# AJH_2v_v1_03.net
KiCad netlist of a schematic drawn in EAGLE
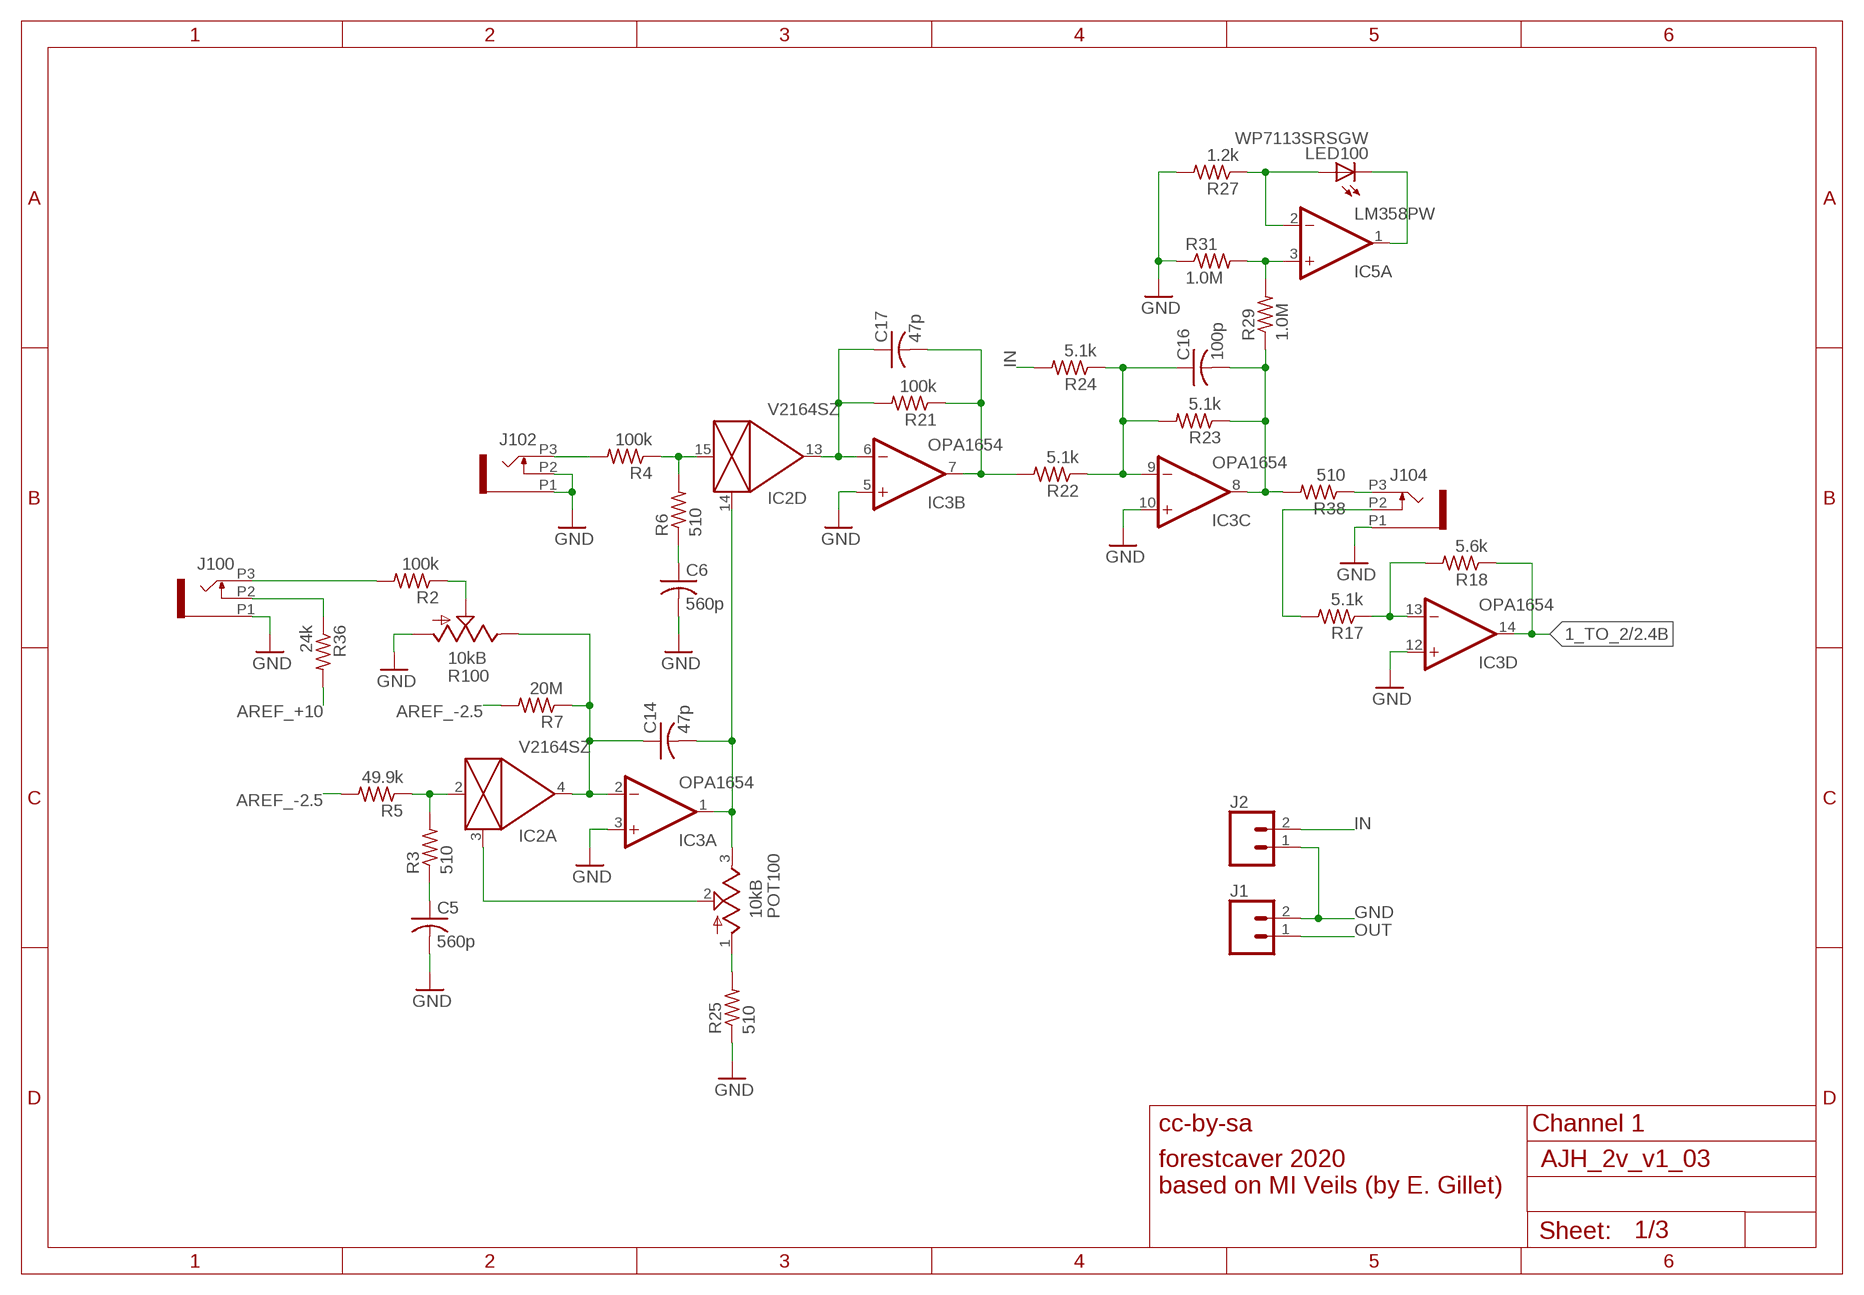
[diagram p0: schematic, sheet 1]
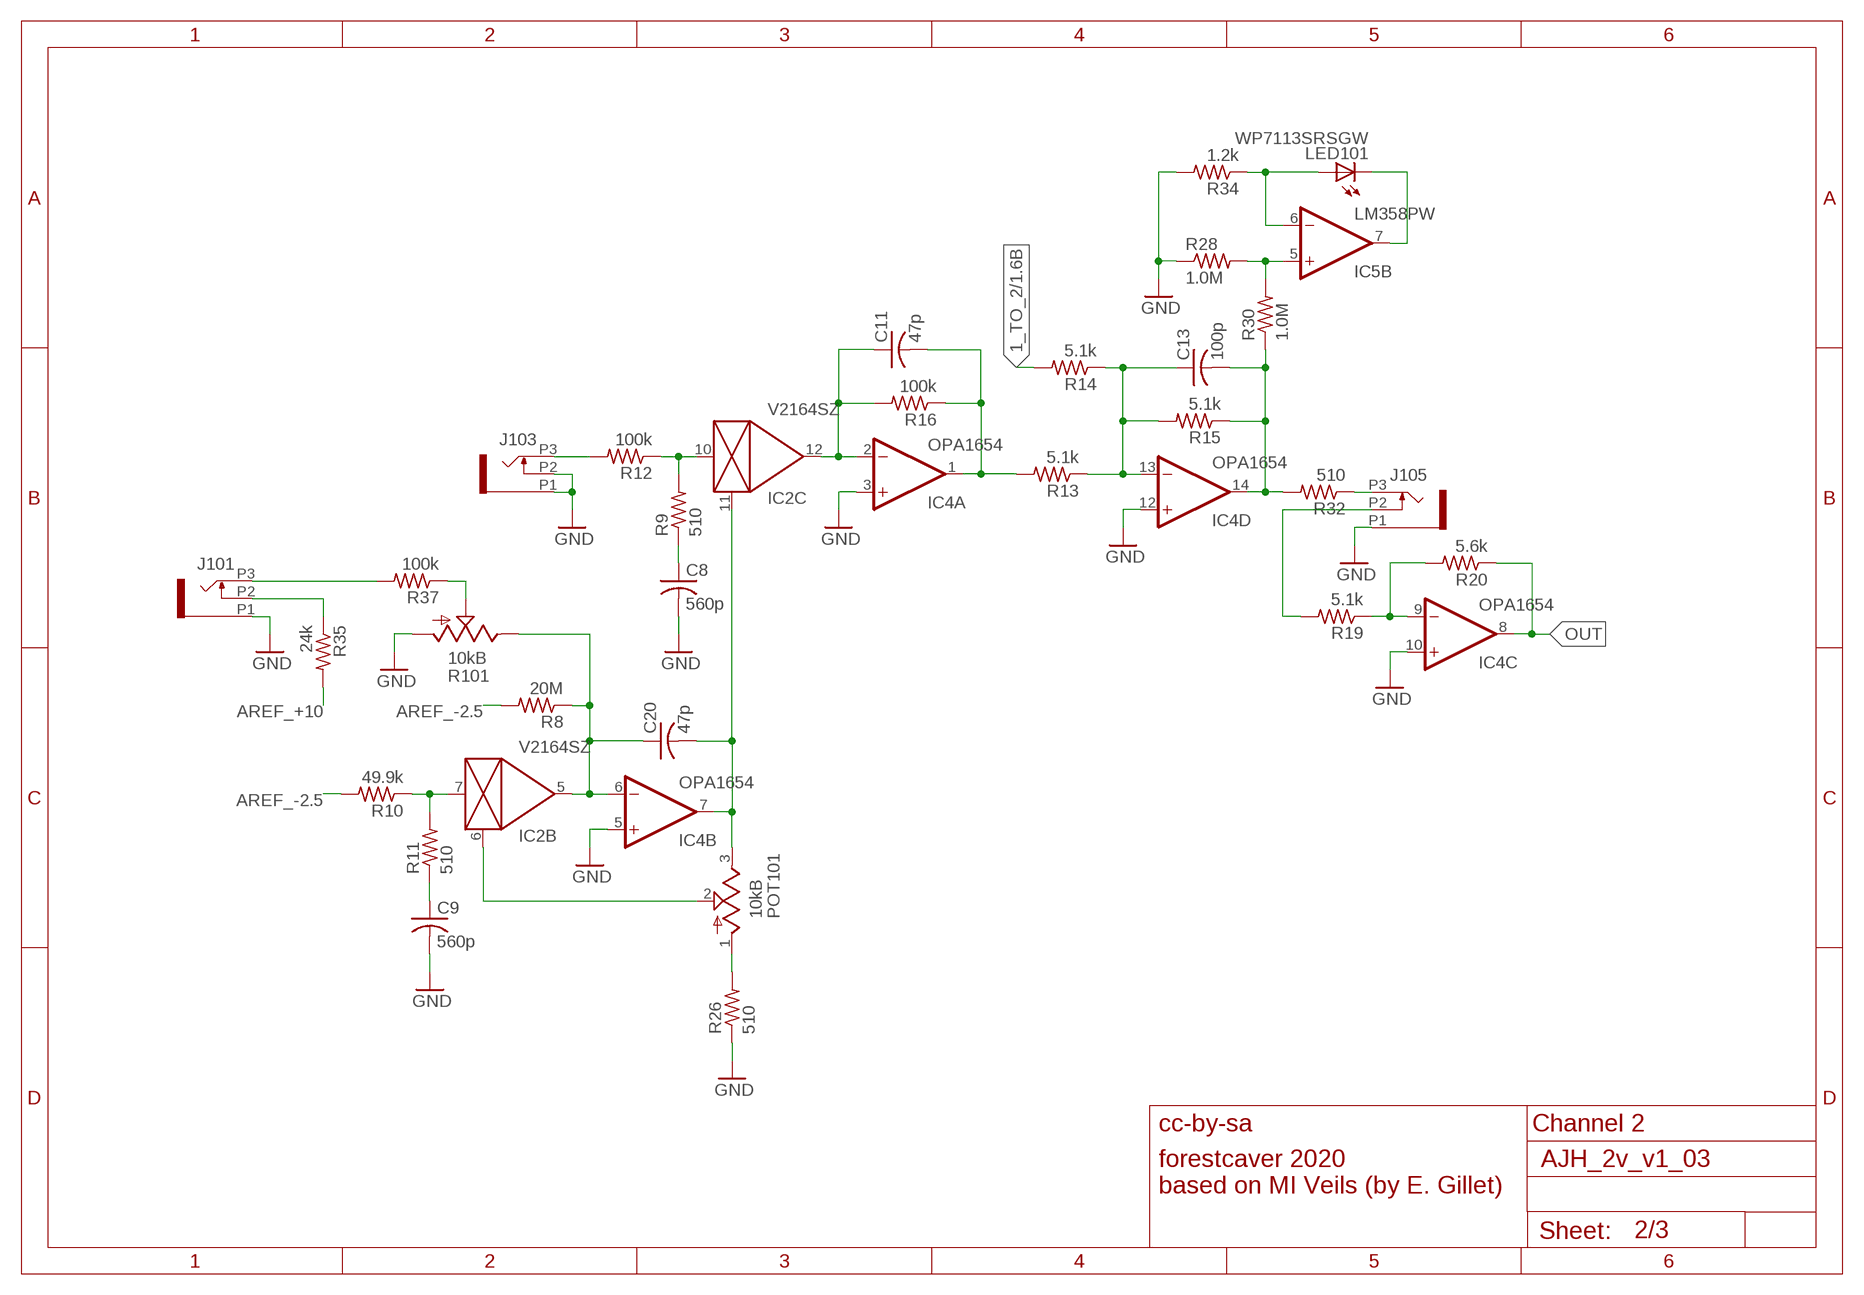
[diagram p1: schematic, sheet 2]
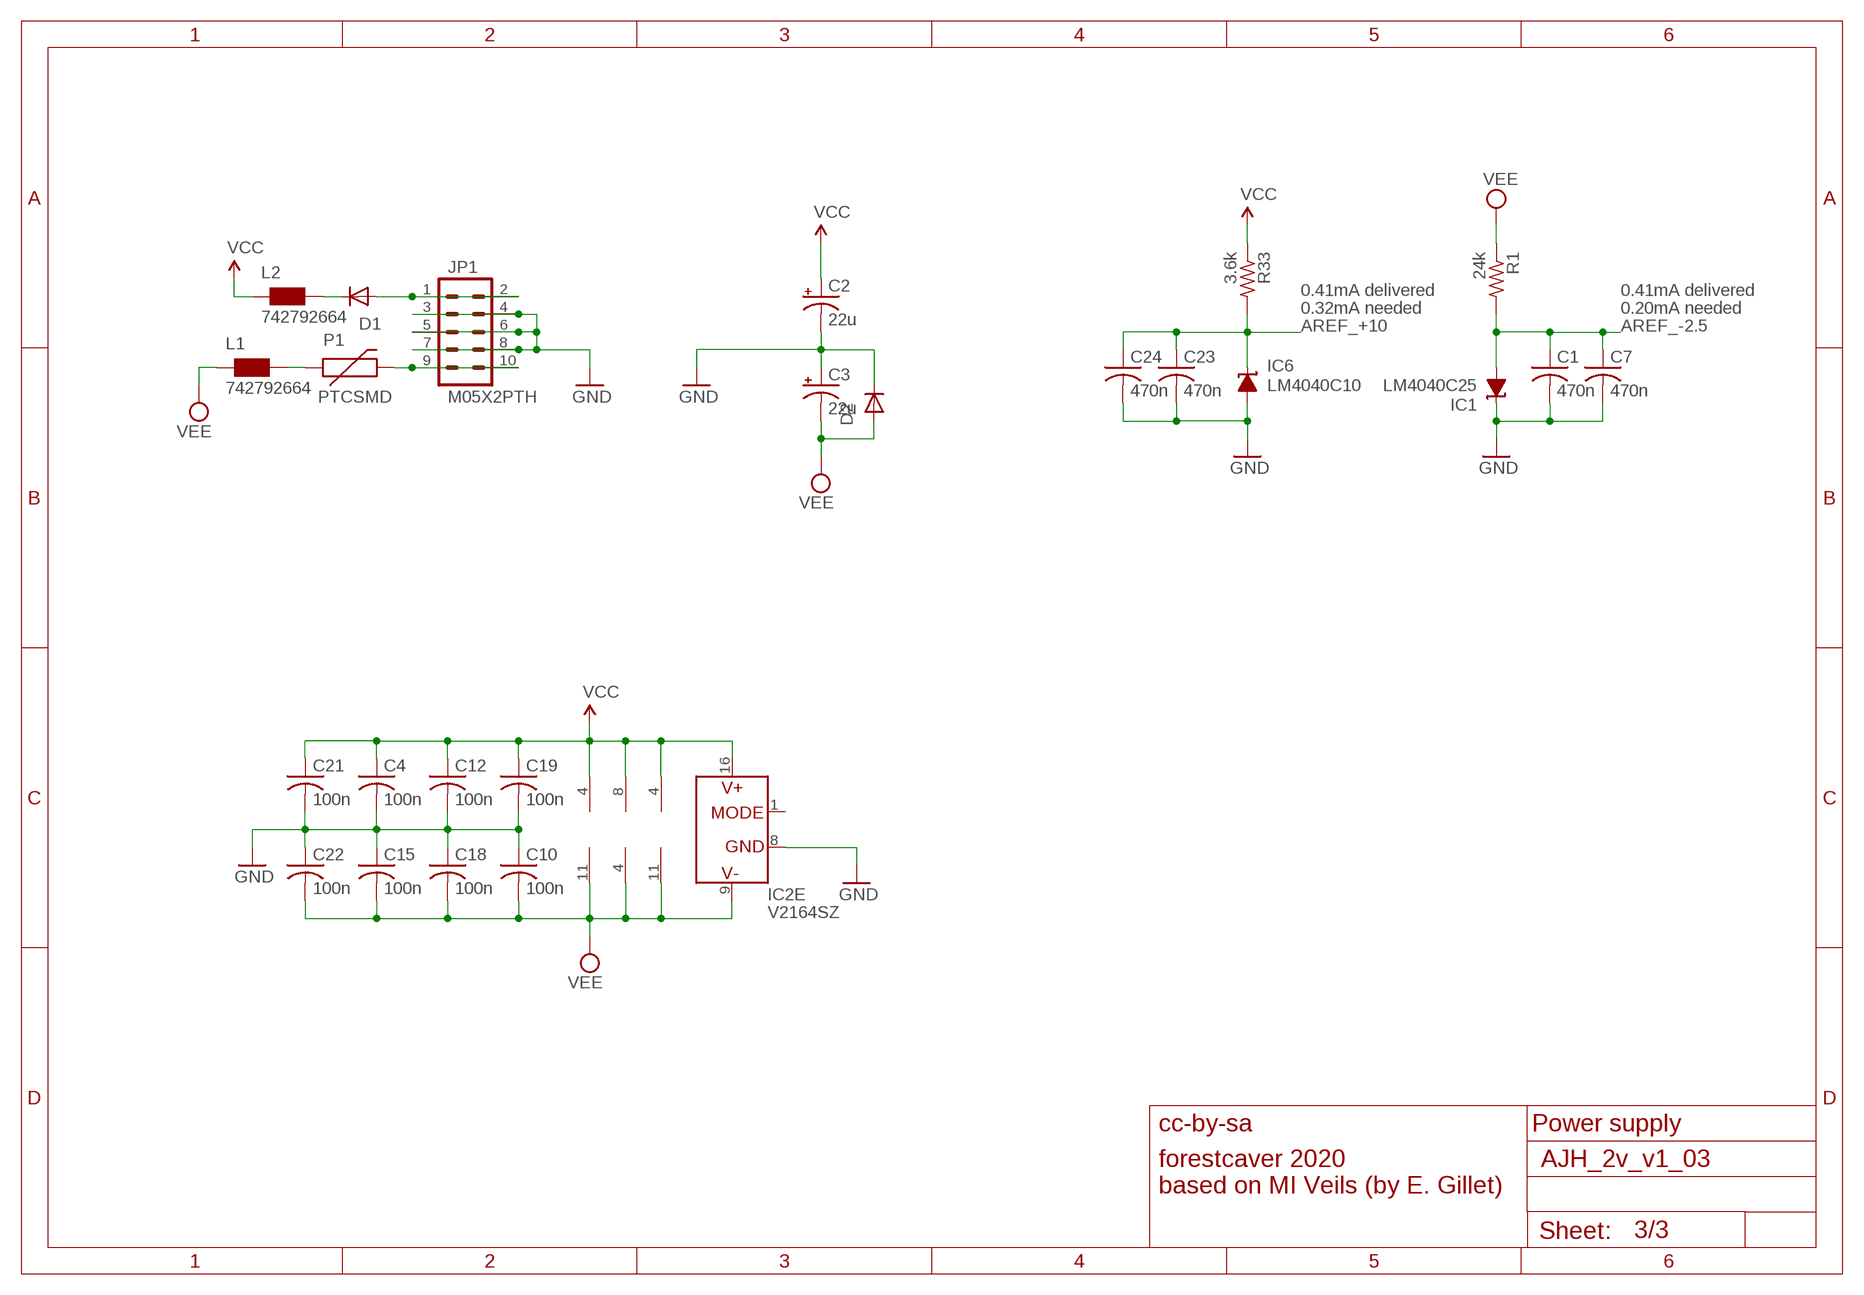
[diagram p2: schematic, sheet 3]

(export (version "E")
  (design (tool "Eeschema 10.0.6"))
  (components
    (comp (ref "C5")
      (value "560p")
      (footprint "eagle-import:C0402")
      (libsource (lib "eagle-import") (part "C-USC0402"))
    )
    (comp (ref "C6")
      (value "560p")
      (footprint "eagle-import:C0402")
      (libsource (lib "eagle-import") (part "C-USC0402"))
    )
    (comp (ref "C14")
      (value "47p")
      (footprint "eagle-import:C0402")
      (libsource (lib "eagle-import") (part "C-USC0402"))
    )
    (comp (ref "C16")
      (value "100p")
      (footprint "eagle-import:C0402")
      (libsource (lib "eagle-import") (part "C-USC0402"))
    )
    (comp (ref "C17")
      (value "47p")
      (footprint "eagle-import:C0402")
      (libsource (lib "eagle-import") (part "C-USC0402"))
    )
    (comp (ref "IC2")
      (value "V2164SZ")
      (footprint "eagle-import:SOIC16N")
      (libsource (lib "eagle-import") (part "SSM2164S"))
    )
    (comp (ref "IC3")
      (value "OPA1654")
      (footprint "eagle-import:TSSOP14")
      (libsource (lib "eagle-import") (part "TL074PW"))
    )
    (comp (ref "IC5")
      (value "LM358PW")
      (footprint "eagle-import:TSSOP8")
      (libsource (lib "eagle-import") (part "TL072PW"))
    )
    (comp (ref "J1")
      (value "CONN_02")
      (footprint "eagle-import:1X02")
      (libsource (lib "eagle-import") (part "CONN_02"))
    )
    (comp (ref "J2")
      (value "CONN_02")
      (footprint "eagle-import:1X02")
      (libsource (lib "eagle-import") (part "CONN_02"))
    )
    (comp (ref "J100")
      (value "PJ301_THONKICONN6")
      (footprint "eagle-import:WQP_PJ_301M6")
      (libsource (lib "eagle-import") (part "PJ301_THONKICONN6"))
    )
    (comp (ref "J102")
      (value "PJ301_THONKICONN6")
      (footprint "eagle-import:WQP_PJ_301M6")
      (libsource (lib "eagle-import") (part "PJ301_THONKICONN6"))
    )
    (comp (ref "J104")
      (value "PJ301_THONKICONN6")
      (footprint "eagle-import:WQP_PJ_301M6")
      (libsource (lib "eagle-import") (part "PJ301_THONKICONN6"))
    )
    (comp (ref "LED100")
      (value "WP7113SRSGW")
      (footprint "eagle-import:LED5MM")
      (libsource (lib "eagle-import") (part "LED5MM"))
    )
    (comp (ref "POT100")
      (value "10kB")
      (footprint "eagle-import:ALPS_POT_NOHOLE")
      (libsource (lib "eagle-import") (part "POT_VERTICALNOHOLE"))
    )
    (comp (ref "R2")
      (value "100k")
      (footprint "eagle-import:R0402")
      (libsource (lib "eagle-import") (part "R-US_R0402"))
    )
    (comp (ref "R3")
      (value "510")
      (footprint "eagle-import:R0402")
      (libsource (lib "eagle-import") (part "R-US_R0402"))
    )
    (comp (ref "R4")
      (value "100k")
      (footprint "eagle-import:R0402")
      (libsource (lib "eagle-import") (part "R-US_R0402"))
    )
    (comp (ref "R5")
      (value "49.9k")
      (footprint "eagle-import:R0402")
      (libsource (lib "eagle-import") (part "R-US_R0402"))
    )
    (comp (ref "R6")
      (value "510")
      (footprint "eagle-import:R0402")
      (libsource (lib "eagle-import") (part "R-US_R0402"))
    )
    (comp (ref "R7")
      (value "20M")
      (footprint "eagle-import:R0402")
      (libsource (lib "eagle-import") (part "R-US_R0402"))
    )
    (comp (ref "R17")
      (value "5.1k")
      (footprint "eagle-import:R0402")
      (libsource (lib "eagle-import") (part "R-US_R0402"))
    )
    (comp (ref "R18")
      (value "5.6k")
      (footprint "eagle-import:R0402")
      (libsource (lib "eagle-import") (part "R-US_R0402"))
    )
    (comp (ref "R21")
      (value "100k")
      (footprint "eagle-import:R0402")
      (libsource (lib "eagle-import") (part "R-US_R0402"))
    )
    (comp (ref "R22")
      (value "5.1k")
      (footprint "eagle-import:R0402")
      (libsource (lib "eagle-import") (part "R-US_R0402"))
    )
    (comp (ref "R23")
      (value "5.1k")
      (footprint "eagle-import:R0402")
      (libsource (lib "eagle-import") (part "R-US_R0402"))
    )
    (comp (ref "R24")
      (value "5.1k")
      (footprint "eagle-import:R0402")
      (libsource (lib "eagle-import") (part "R-US_R0402"))
    )
    (comp (ref "R25")
      (value "510")
      (footprint "eagle-import:R0402")
      (libsource (lib "eagle-import") (part "R-US_R0402"))
    )
    (comp (ref "R27")
      (value "1.2k")
      (footprint "eagle-import:R0402")
      (libsource (lib "eagle-import") (part "R-US_R0402"))
    )
    (comp (ref "R29")
      (value "1.0M")
      (footprint "eagle-import:R0402")
      (libsource (lib "eagle-import") (part "R-US_R0402"))
    )
    (comp (ref "R31")
      (value "1.0M")
      (footprint "eagle-import:R0402")
      (libsource (lib "eagle-import") (part "R-US_R0402"))
    )
    (comp (ref "R36")
      (value "24k")
      (footprint "eagle-import:R0402")
      (libsource (lib "eagle-import") (part "R-US_R0402"))
    )
    (comp (ref "R38")
      (value "510")
      (footprint "eagle-import:R0402")
      (libsource (lib "eagle-import") (part "R-US_R0402"))
    )
    (comp (ref "R100")
      (value "10kB")
      (footprint "eagle-import:ALPS_POT_VERTICAL_PS")
      (libsource (lib "eagle-import") (part "POT_USVERTICAL_PS"))
    )
    (comp (ref "C1")
      (value "470n")
      (footprint "eagle-import:C0402")
      (libsource (lib "eagle-import") (part "C-USC0402"))
    )
    (comp (ref "C2")
      (value "22u")
      (footprint "eagle-import:PANASONIC_B")
      (libsource (lib "eagle-import") (part "CPOL-USB"))
    )
    (comp (ref "C3")
      (value "22u")
      (footprint "eagle-import:PANASONIC_B")
      (libsource (lib "eagle-import") (part "CPOL-USB"))
    )
    (comp (ref "C4")
      (value "100n")
      (footprint "eagle-import:C0402")
      (libsource (lib "eagle-import") (part "C-USC0402"))
    )
    (comp (ref "C7")
      (value "470n")
      (footprint "eagle-import:C0402")
      (libsource (lib "eagle-import") (part "C-USC0402"))
    )
    (comp (ref "C10")
      (value "100n")
      (footprint "eagle-import:C0402")
      (libsource (lib "eagle-import") (part "C-USC0402"))
    )
    (comp (ref "C12")
      (value "100n")
      (footprint "eagle-import:C0402")
      (libsource (lib "eagle-import") (part "C-USC0402"))
    )
    (comp (ref "C15")
      (value "100n")
      (footprint "eagle-import:C0402")
      (libsource (lib "eagle-import") (part "C-USC0402"))
    )
    (comp (ref "C18")
      (value "100n")
      (footprint "eagle-import:C0402")
      (libsource (lib "eagle-import") (part "C-USC0402"))
    )
    (comp (ref "C19")
      (value "100n")
      (footprint "eagle-import:C0402")
      (libsource (lib "eagle-import") (part "C-USC0402"))
    )
    (comp (ref "C21")
      (value "100n")
      (footprint "eagle-import:C0402")
      (libsource (lib "eagle-import") (part "C-USC0402"))
    )
    (comp (ref "C22")
      (value "100n")
      (footprint "eagle-import:C0402")
      (libsource (lib "eagle-import") (part "C-USC0402"))
    )
    (comp (ref "C23")
      (value "470n")
      (footprint "eagle-import:C0402")
      (libsource (lib "eagle-import") (part "C-USC0402"))
    )
    (comp (ref "C24")
      (value "470n")
      (footprint "eagle-import:C0402")
      (libsource (lib "eagle-import") (part "C-USC0402"))
    )
    (comp (ref "D1")
      (value "1N5819HW")
      (footprint "eagle-import:SOD123")
      (libsource (lib "eagle-import") (part "DIODE-SOD123"))
    )
    (comp (ref "D2")
      (value "1N5819HW")
      (footprint "eagle-import:SOD123")
      (libsource (lib "eagle-import") (part "DIODE-SOD123"))
    )
    (comp (ref "IC1")
      (value "LM4040C25")
      (footprint "eagle-import:DBZ_R-PDSO-G3")
      (libsource (lib "eagle-import") (part "LM4041DBZB12"))
    )
    (comp (ref "IC4")
      (value "OPA1654")
      (footprint "eagle-import:TSSOP14")
      (libsource (lib "eagle-import") (part "TL074PW"))
    )
    (comp (ref "IC6")
      (value "LM4040C10")
      (footprint "eagle-import:DBZ_R-PDSO-G3")
      (libsource (lib "eagle-import") (part "LM4041DBZB12"))
    )
    (comp (ref "JP1")
      (value "M05X2PTH")
      (footprint "eagle-import:AVR_ICSP")
      (libsource (lib "eagle-import") (part "M05X2PTH"))
    )
    (comp (ref "L1")
      (value "742792664")
      (footprint "eagle-import:0603")
      (libsource (lib "eagle-import") (part "WE-CBF_0603"))
    )
    (comp (ref "L2")
      (value "742792664")
      (footprint "eagle-import:0603")
      (libsource (lib "eagle-import") (part "WE-CBF_0603"))
    )
    (comp (ref "P1")
      (value "PTCSMD")
      (footprint "eagle-import:PTC-1206")
      (libsource (lib "eagle-import") (part "PTCSMD"))
    )
    (comp (ref "R1")
      (value "24k")
      (footprint "eagle-import:R0402")
      (libsource (lib "eagle-import") (part "R-US_R0402"))
    )
    (comp (ref "R33")
      (value "3.6k")
      (footprint "eagle-import:R0402")
      (libsource (lib "eagle-import") (part "R-US_R0402"))
    )
    (comp (ref "C8")
      (value "560p")
      (footprint "eagle-import:C0402")
      (libsource (lib "eagle-import") (part "C-USC0402"))
    )
    (comp (ref "C9")
      (value "560p")
      (footprint "eagle-import:C0402")
      (libsource (lib "eagle-import") (part "C-USC0402"))
    )
    (comp (ref "C11")
      (value "47p")
      (footprint "eagle-import:C0402")
      (libsource (lib "eagle-import") (part "C-USC0402"))
    )
    (comp (ref "C13")
      (value "100p")
      (footprint "eagle-import:C0402")
      (libsource (lib "eagle-import") (part "C-USC0402"))
    )
    (comp (ref "C20")
      (value "47p")
      (footprint "eagle-import:C0402")
      (libsource (lib "eagle-import") (part "C-USC0402"))
    )
    (comp (ref "J101")
      (value "PJ301_THONKICONN6")
      (footprint "eagle-import:WQP_PJ_301M6")
      (libsource (lib "eagle-import") (part "PJ301_THONKICONN6"))
    )
    (comp (ref "J103")
      (value "PJ301_THONKICONN6")
      (footprint "eagle-import:WQP_PJ_301M6")
      (libsource (lib "eagle-import") (part "PJ301_THONKICONN6"))
    )
    (comp (ref "J105")
      (value "PJ301_THONKICONN6")
      (footprint "eagle-import:WQP_PJ_301M6")
      (libsource (lib "eagle-import") (part "PJ301_THONKICONN6"))
    )
    (comp (ref "LED101")
      (value "WP7113SRSGW")
      (footprint "eagle-import:LED5MM")
      (libsource (lib "eagle-import") (part "LED5MM"))
    )
    (comp (ref "POT101")
      (value "10kB")
      (footprint "eagle-import:ALPS_POT_NOHOLE")
      (libsource (lib "eagle-import") (part "POT_VERTICALNOHOLE"))
    )
    (comp (ref "R8")
      (value "20M")
      (footprint "eagle-import:R0402")
      (libsource (lib "eagle-import") (part "R-US_R0402"))
    )
    (comp (ref "R9")
      (value "510")
      (footprint "eagle-import:R0402")
      (libsource (lib "eagle-import") (part "R-US_R0402"))
    )
    (comp (ref "R10")
      (value "49.9k")
      (footprint "eagle-import:R0402")
      (libsource (lib "eagle-import") (part "R-US_R0402"))
    )
    (comp (ref "R11")
      (value "510")
      (footprint "eagle-import:R0402")
      (libsource (lib "eagle-import") (part "R-US_R0402"))
    )
    (comp (ref "R12")
      (value "100k")
      (footprint "eagle-import:R0402")
      (libsource (lib "eagle-import") (part "R-US_R0402"))
    )
    (comp (ref "R13")
      (value "5.1k")
      (footprint "eagle-import:R0402")
      (libsource (lib "eagle-import") (part "R-US_R0402"))
    )
    (comp (ref "R14")
      (value "5.1k")
      (footprint "eagle-import:R0402")
      (libsource (lib "eagle-import") (part "R-US_R0402"))
    )
    (comp (ref "R15")
      (value "5.1k")
      (footprint "eagle-import:R0402")
      (libsource (lib "eagle-import") (part "R-US_R0402"))
    )
    (comp (ref "R16")
      (value "100k")
      (footprint "eagle-import:R0402")
      (libsource (lib "eagle-import") (part "R-US_R0402"))
    )
    (comp (ref "R19")
      (value "5.1k")
      (footprint "eagle-import:R0402")
      (libsource (lib "eagle-import") (part "R-US_R0402"))
    )
    (comp (ref "R20")
      (value "5.6k")
      (footprint "eagle-import:R0402")
      (libsource (lib "eagle-import") (part "R-US_R0402"))
    )
    (comp (ref "R26")
      (value "510")
      (footprint "eagle-import:R0402")
      (libsource (lib "eagle-import") (part "R-US_R0402"))
    )
    (comp (ref "R28")
      (value "1.0M")
      (footprint "eagle-import:R0402")
      (libsource (lib "eagle-import") (part "R-US_R0402"))
    )
    (comp (ref "R30")
      (value "1.0M")
      (footprint "eagle-import:R0402")
      (libsource (lib "eagle-import") (part "R-US_R0402"))
    )
    (comp (ref "R32")
      (value "510")
      (footprint "eagle-import:R0402")
      (libsource (lib "eagle-import") (part "R-US_R0402"))
    )
    (comp (ref "R34")
      (value "1.2k")
      (footprint "eagle-import:R0402")
      (libsource (lib "eagle-import") (part "R-US_R0402"))
    )
    (comp (ref "R35")
      (value "24k")
      (footprint "eagle-import:R0402")
      (libsource (lib "eagle-import") (part "R-US_R0402"))
    )
    (comp (ref "R37")
      (value "100k")
      (footprint "eagle-import:R0402")
      (libsource (lib "eagle-import") (part "R-US_R0402"))
    )
    (comp (ref "R101")
      (value "10kB")
      (footprint "eagle-import:ALPS_POT_VERTICAL_PS")
      (libsource (lib "eagle-import") (part "POT_USVERTICAL_PS"))
    )
  )
  (nets
    (net (code "1") (name "1_TO_2") (class "Default")
      (node (ref "IC3") (pin "14") (pinfunction "OUT_14") (pintype "output"))
      (node (ref "R14") (pin "2") (pinfunction "2_2") (pintype "passive"))
      (node (ref "R18") (pin "1") (pinfunction "1_1") (pintype "passive"))
    )
    (net (code "2") (name "AREF_+10") (class "Default")
      (node (ref "C23") (pin "1") (pinfunction "1_1") (pintype "passive"))
      (node (ref "C24") (pin "1") (pinfunction "1_1") (pintype "passive"))
      (node (ref "IC6") (pin "1") (pinfunction "C_1") (pintype "passive"))
      (node (ref "R33") (pin "2") (pinfunction "2_2") (pintype "passive"))
      (node (ref "R35") (pin "2") (pinfunction "2_2") (pintype "passive"))
      (node (ref "R36") (pin "2") (pinfunction "2_2") (pintype "passive"))
    )
    (net (code "3") (name "AREF_-2.5") (class "Default")
      (node (ref "C1") (pin "1") (pinfunction "1_1") (pintype "passive"))
      (node (ref "C7") (pin "1") (pinfunction "1_1") (pintype "passive"))
      (node (ref "IC1") (pin "2") (pinfunction "A_2") (pintype "passive"))
      (node (ref "R1") (pin "2") (pinfunction "2_2") (pintype "passive"))
      (node (ref "R10") (pin "2") (pinfunction "2_2") (pintype "passive"))
      (node (ref "R5") (pin "2") (pinfunction "2_2") (pintype "passive"))
      (node (ref "R7") (pin "2") (pinfunction "2_2") (pintype "passive"))
      (node (ref "R8") (pin "2") (pinfunction "2_2") (pintype "passive"))
    )
    (net (code "4") (name "GND") (class "Default")
      (node (ref "C1") (pin "2") (pinfunction "2_2") (pintype "passive"))
      (node (ref "C10") (pin "1") (pinfunction "1_1") (pintype "passive"))
      (node (ref "C12") (pin "2") (pinfunction "2_2") (pintype "passive"))
      (node (ref "C15") (pin "1") (pinfunction "1_1") (pintype "passive"))
      (node (ref "C18") (pin "1") (pinfunction "1_1") (pintype "passive"))
      (node (ref "C19") (pin "2") (pinfunction "2_2") (pintype "passive"))
      (node (ref "C2") (pin "-") (pinfunction "-_-") (pintype "passive"))
      (node (ref "C21") (pin "2") (pinfunction "2_2") (pintype "passive"))
      (node (ref "C22") (pin "1") (pinfunction "1_1") (pintype "passive"))
      (node (ref "C23") (pin "2") (pinfunction "2_2") (pintype "passive"))
      (node (ref "C24") (pin "2") (pinfunction "2_2") (pintype "passive"))
      (node (ref "C3") (pin "+") (pinfunction "+_+") (pintype "passive"))
      (node (ref "C4") (pin "2") (pinfunction "2_2") (pintype "passive"))
      (node (ref "C5") (pin "2") (pinfunction "2_2") (pintype "passive"))
      (node (ref "C6") (pin "2") (pinfunction "2_2") (pintype "passive"))
      (node (ref "C7") (pin "2") (pinfunction "2_2") (pintype "passive"))
      (node (ref "C8") (pin "2") (pinfunction "2_2") (pintype "passive"))
      (node (ref "C9") (pin "2") (pinfunction "2_2") (pintype "passive"))
      (node (ref "D2") (pin "C") (pinfunction "C_C") (pintype "passive"))
      (node (ref "IC1") (pin "1") (pinfunction "C_1") (pintype "passive"))
      (node (ref "IC2") (pin "8") (pinfunction "GND_8") (pintype "power_in"))
      (node (ref "IC3") (pin "10") (pinfunction "+IN_10") (pintype "input"))
      (node (ref "IC3") (pin "12") (pinfunction "+IN_12") (pintype "input"))
      (node (ref "IC3") (pin "3") (pinfunction "+IN_3") (pintype "input"))
      (node (ref "IC3") (pin "5") (pinfunction "+IN_5") (pintype "input"))
      (node (ref "IC4") (pin "10") (pinfunction "+IN_10") (pintype "input"))
      (node (ref "IC4") (pin "12") (pinfunction "+IN_12") (pintype "input"))
      (node (ref "IC4") (pin "3") (pinfunction "+IN_3") (pintype "input"))
      (node (ref "IC4") (pin "5") (pinfunction "+IN_5") (pintype "input"))
      (node (ref "IC6") (pin "2") (pinfunction "A_2") (pintype "passive"))
      (node (ref "J1") (pin "2") (pinfunction "2_2") (pintype "passive"))
      (node (ref "J100") (pin "P1") (pinfunction "1_P1") (pintype "passive"))
      (node (ref "J101") (pin "P1") (pinfunction "1_P1") (pintype "passive"))
      (node (ref "J102") (pin "P1") (pinfunction "1_P1") (pintype "passive"))
      (node (ref "J102") (pin "P2") (pinfunction "2_P2") (pintype "passive"))
      (node (ref "J103") (pin "P1") (pinfunction "1_P1") (pintype "passive"))
      (node (ref "J103") (pin "P2") (pinfunction "2_P2") (pintype "passive"))
      (node (ref "J104") (pin "P1") (pinfunction "1_P1") (pintype "passive"))
      (node (ref "J105") (pin "P1") (pinfunction "1_P1") (pintype "passive"))
      (node (ref "J2") (pin "1") (pinfunction "1_1") (pintype "passive"))
      (node (ref "JP1") (pin "3") (pinfunction "3_3") (pintype "passive"))
      (node (ref "JP1") (pin "4") (pinfunction "4_4") (pintype "passive"))
      (node (ref "JP1") (pin "5") (pinfunction "5_5") (pintype "passive"))
      (node (ref "JP1") (pin "6") (pinfunction "6_6") (pintype "passive"))
      (node (ref "JP1") (pin "7") (pinfunction "7_7") (pintype "passive"))
      (node (ref "JP1") (pin "8") (pinfunction "8_8") (pintype "passive"))
      (node (ref "R100") (pin "P$3") (pinfunction "A_P$3") (pintype "passive"))
      (node (ref "R101") (pin "P$3") (pinfunction "A_P$3") (pintype "passive"))
      (node (ref "R25") (pin "1") (pinfunction "1_1") (pintype "passive"))
      (node (ref "R26") (pin "1") (pinfunction "1_1") (pintype "passive"))
      (node (ref "R27") (pin "2") (pinfunction "2_2") (pintype "passive"))
      (node (ref "R28") (pin "1") (pinfunction "1_1") (pintype "passive"))
      (node (ref "R31") (pin "1") (pinfunction "1_1") (pintype "passive"))
      (node (ref "R34") (pin "2") (pinfunction "2_2") (pintype "passive"))
    )
    (net (code "5") (name "IN") (class "Default")
      (node (ref "J2") (pin "2") (pinfunction "2_2") (pintype "passive"))
      (node (ref "R24") (pin "2") (pinfunction "2_2") (pintype "passive"))
    )
    (net (code "6") (name "Net-(C5-Pad1)") (class "Default")
      (node (ref "C5") (pin "1") (pinfunction "1_1") (pintype "passive"))
      (node (ref "R3") (pin "1") (pinfunction "1_1") (pintype "passive"))
    )
    (net (code "7") (name "Net-(C6-Pad1)") (class "Default")
      (node (ref "C6") (pin "1") (pinfunction "1_1") (pintype "passive"))
      (node (ref "R6") (pin "1") (pinfunction "1_1") (pintype "passive"))
    )
    (net (code "8") (name "Net-(C8-Pad1)") (class "Default")
      (node (ref "C8") (pin "1") (pinfunction "1_1") (pintype "passive"))
      (node (ref "R9") (pin "1") (pinfunction "1_1") (pintype "passive"))
    )
    (net (code "9") (name "Net-(C9-Pad1)") (class "Default")
      (node (ref "C9") (pin "1") (pinfunction "1_1") (pintype "passive"))
      (node (ref "R11") (pin "1") (pinfunction "1_1") (pintype "passive"))
    )
    (net (code "10") (name "Net-(D1-PadA)") (class "Default")
      (node (ref "D1") (pin "A") (pinfunction "A_A") (pintype "passive"))
      (node (ref "JP1") (pin "1") (pinfunction "1_1") (pintype "passive"))
      (node (ref "JP1") (pin "2") (pinfunction "2_2") (pintype "passive"))
    )
    (net (code "11") (name "Net-(D1-PadC)") (class "Default")
      (node (ref "D1") (pin "C") (pinfunction "C_C") (pintype "passive"))
      (node (ref "L2") (pin "2") (pinfunction "2_2") (pintype "passive"))
    )
    (net (code "12") (name "Net-(IC2A-CTRL)") (class "Default")
      (node (ref "IC2") (pin "3") (pinfunction "CTRL_3") (pintype "input"))
      (node (ref "POT100") (pin "2") (pinfunction "W_2") (pintype "passive"))
    )
    (net (code "13") (name "Net-(IC2A-IN)") (class "Default")
      (node (ref "IC2") (pin "2") (pinfunction "IN_2") (pintype "input"))
      (node (ref "R3") (pin "2") (pinfunction "2_2") (pintype "passive"))
      (node (ref "R5") (pin "1") (pinfunction "1_1") (pintype "passive"))
    )
    (net (code "14") (name "Net-(IC2A-OUT)") (class "Default")
      (node (ref "C14") (pin "1") (pinfunction "1_1") (pintype "passive"))
      (node (ref "IC2") (pin "4") (pinfunction "OUT_4") (pintype "output"))
      (node (ref "IC3") (pin "2") (pinfunction "-IN_2") (pintype "input"))
      (node (ref "R100") (pin "P$1") (pinfunction "E_P$1") (pintype "passive"))
      (node (ref "R7") (pin "1") (pinfunction "1_1") (pintype "passive"))
    )
    (net (code "15") (name "Net-(IC2B-CTRL)") (class "Default")
      (node (ref "IC2") (pin "6") (pinfunction "CTRL_6") (pintype "input"))
      (node (ref "POT101") (pin "2") (pinfunction "W_2") (pintype "passive"))
    )
    (net (code "16") (name "Net-(IC2B-IN)") (class "Default")
      (node (ref "IC2") (pin "7") (pinfunction "IN_7") (pintype "input"))
      (node (ref "R10") (pin "1") (pinfunction "1_1") (pintype "passive"))
      (node (ref "R11") (pin "2") (pinfunction "2_2") (pintype "passive"))
    )
    (net (code "17") (name "Net-(IC2B-OUT)") (class "Default")
      (node (ref "C20") (pin "1") (pinfunction "1_1") (pintype "passive"))
      (node (ref "IC2") (pin "5") (pinfunction "OUT_5") (pintype "output"))
      (node (ref "IC4") (pin "6") (pinfunction "-IN_6") (pintype "input"))
      (node (ref "R101") (pin "P$1") (pinfunction "E_P$1") (pintype "passive"))
      (node (ref "R8") (pin "1") (pinfunction "1_1") (pintype "passive"))
    )
    (net (code "18") (name "Net-(IC2C-CTRL)") (class "Default")
      (node (ref "C20") (pin "2") (pinfunction "2_2") (pintype "passive"))
      (node (ref "IC2") (pin "11") (pinfunction "CTRL_11") (pintype "input"))
      (node (ref "IC4") (pin "7") (pinfunction "OUT_7") (pintype "output"))
      (node (ref "POT101") (pin "3") (pinfunction "B_3") (pintype "passive"))
    )
    (net (code "19") (name "Net-(IC2C-IN)") (class "Default")
      (node (ref "IC2") (pin "10") (pinfunction "IN_10") (pintype "input"))
      (node (ref "R12") (pin "1") (pinfunction "1_1") (pintype "passive"))
      (node (ref "R9") (pin "2") (pinfunction "2_2") (pintype "passive"))
    )
    (net (code "20") (name "Net-(IC2C-OUT)") (class "Default")
      (node (ref "C11") (pin "1") (pinfunction "1_1") (pintype "passive"))
      (node (ref "IC2") (pin "12") (pinfunction "OUT_12") (pintype "output"))
      (node (ref "IC4") (pin "2") (pinfunction "-IN_2") (pintype "input"))
      (node (ref "R16") (pin "2") (pinfunction "2_2") (pintype "passive"))
    )
    (net (code "21") (name "Net-(IC2D-CTRL)") (class "Default")
      (node (ref "C14") (pin "2") (pinfunction "2_2") (pintype "passive"))
      (node (ref "IC2") (pin "14") (pinfunction "CTRL_14") (pintype "input"))
      (node (ref "IC3") (pin "1") (pinfunction "OUT_1") (pintype "output"))
      (node (ref "POT100") (pin "3") (pinfunction "B_3") (pintype "passive"))
    )
    (net (code "22") (name "Net-(IC2D-IN)") (class "Default")
      (node (ref "IC2") (pin "15") (pinfunction "IN_15") (pintype "input"))
      (node (ref "R4") (pin "1") (pinfunction "1_1") (pintype "passive"))
      (node (ref "R6") (pin "2") (pinfunction "2_2") (pintype "passive"))
    )
    (net (code "23") (name "Net-(IC2D-OUT)") (class "Default")
      (node (ref "C17") (pin "1") (pinfunction "1_1") (pintype "passive"))
      (node (ref "IC2") (pin "13") (pinfunction "OUT_13") (pintype "output"))
      (node (ref "IC3") (pin "6") (pinfunction "-IN_6") (pintype "input"))
      (node (ref "R21") (pin "2") (pinfunction "2_2") (pintype "passive"))
    )
    (net (code "24") (name "Net-(IC3B-OUT)") (class "Default")
      (node (ref "C17") (pin "2") (pinfunction "2_2") (pintype "passive"))
      (node (ref "IC3") (pin "7") (pinfunction "OUT_7") (pintype "output"))
      (node (ref "R21") (pin "1") (pinfunction "1_1") (pintype "passive"))
      (node (ref "R22") (pin "2") (pinfunction "2_2") (pintype "passive"))
    )
    (net (code "25") (name "Net-(IC3C--IN)") (class "Default")
      (node (ref "C16") (pin "1") (pinfunction "1_1") (pintype "passive"))
      (node (ref "IC3") (pin "9") (pinfunction "-IN_9") (pintype "input"))
      (node (ref "R22") (pin "1") (pinfunction "1_1") (pintype "passive"))
      (node (ref "R23") (pin "2") (pinfunction "2_2") (pintype "passive"))
      (node (ref "R24") (pin "1") (pinfunction "1_1") (pintype "passive"))
    )
    (net (code "26") (name "Net-(IC3C-OUT)") (class "Default")
      (node (ref "C16") (pin "2") (pinfunction "2_2") (pintype "passive"))
      (node (ref "IC3") (pin "8") (pinfunction "OUT_8") (pintype "output"))
      (node (ref "R23") (pin "1") (pinfunction "1_1") (pintype "passive"))
      (node (ref "R29") (pin "1") (pinfunction "1_1") (pintype "passive"))
      (node (ref "R38") (pin "2") (pinfunction "2_2") (pintype "passive"))
    )
    (net (code "27") (name "Net-(IC3D--IN)") (class "Default")
      (node (ref "IC3") (pin "13") (pinfunction "-IN_13") (pintype "input"))
      (node (ref "R17") (pin "1") (pinfunction "1_1") (pintype "passive"))
      (node (ref "R18") (pin "2") (pinfunction "2_2") (pintype "passive"))
    )
    (net (code "28") (name "Net-(IC4A-OUT)") (class "Default")
      (node (ref "C11") (pin "2") (pinfunction "2_2") (pintype "passive"))
      (node (ref "IC4") (pin "1") (pinfunction "OUT_1") (pintype "output"))
      (node (ref "R13") (pin "2") (pinfunction "2_2") (pintype "passive"))
      (node (ref "R16") (pin "1") (pinfunction "1_1") (pintype "passive"))
    )
    (net (code "29") (name "Net-(IC4C--IN)") (class "Default")
      (node (ref "IC4") (pin "9") (pinfunction "-IN_9") (pintype "input"))
      (node (ref "R19") (pin "1") (pinfunction "1_1") (pintype "passive"))
      (node (ref "R20") (pin "2") (pinfunction "2_2") (pintype "passive"))
    )
    (net (code "30") (name "Net-(IC4D--IN)") (class "Default")
      (node (ref "C13") (pin "1") (pinfunction "1_1") (pintype "passive"))
      (node (ref "IC4") (pin "13") (pinfunction "-IN_13") (pintype "input"))
      (node (ref "R13") (pin "1") (pinfunction "1_1") (pintype "passive"))
      (node (ref "R14") (pin "1") (pinfunction "1_1") (pintype "passive"))
      (node (ref "R15") (pin "2") (pinfunction "2_2") (pintype "passive"))
    )
    (net (code "31") (name "Net-(IC4D-OUT)") (class "Default")
      (node (ref "C13") (pin "2") (pinfunction "2_2") (pintype "passive"))
      (node (ref "IC4") (pin "14") (pinfunction "OUT_14") (pintype "output"))
      (node (ref "R15") (pin "1") (pinfunction "1_1") (pintype "passive"))
      (node (ref "R30") (pin "1") (pinfunction "1_1") (pintype "passive"))
      (node (ref "R32") (pin "2") (pinfunction "2_2") (pintype "passive"))
    )
    (net (code "32") (name "Net-(IC5A-+IN)") (class "Default")
      (node (ref "IC5") (pin "3") (pinfunction "+IN_3") (pintype "input"))
      (node (ref "R29") (pin "2") (pinfunction "2_2") (pintype "passive"))
      (node (ref "R31") (pin "2") (pinfunction "2_2") (pintype "passive"))
    )
    (net (code "33") (name "Net-(IC5A--IN)") (class "Default")
      (node (ref "IC5") (pin "2") (pinfunction "-IN_2") (pintype "input"))
      (node (ref "LED100") (pin "A") (pinfunction "A_A") (pintype "passive"))
      (node (ref "R27") (pin "1") (pinfunction "1_1") (pintype "passive"))
    )
    (net (code "34") (name "Net-(IC5A-OUT)") (class "Default")
      (node (ref "IC5") (pin "1") (pinfunction "OUT_1") (pintype "output"))
      (node (ref "LED100") (pin "K") (pinfunction "C_K") (pintype "passive"))
    )
    (net (code "35") (name "Net-(IC5B-+IN)") (class "Default")
      (node (ref "IC5") (pin "5") (pinfunction "+IN_5") (pintype "input"))
      (node (ref "R28") (pin "2") (pinfunction "2_2") (pintype "passive"))
      (node (ref "R30") (pin "2") (pinfunction "2_2") (pintype "passive"))
    )
    (net (code "36") (name "Net-(IC5B--IN)") (class "Default")
      (node (ref "IC5") (pin "6") (pinfunction "-IN_6") (pintype "input"))
      (node (ref "LED101") (pin "A") (pinfunction "A_A") (pintype "passive"))
      (node (ref "R34") (pin "1") (pinfunction "1_1") (pintype "passive"))
    )
    (net (code "37") (name "Net-(IC5B-OUT)") (class "Default")
      (node (ref "IC5") (pin "7") (pinfunction "OUT_7") (pintype "output"))
      (node (ref "LED101") (pin "K") (pinfunction "C_K") (pintype "passive"))
    )
    (net (code "38") (name "Net-(J100-2)") (class "Default")
      (node (ref "J100") (pin "P2") (pinfunction "2_P2") (pintype "passive"))
      (node (ref "R36") (pin "1") (pinfunction "1_1") (pintype "passive"))
    )
    (net (code "39") (name "Net-(J100-3)") (class "Default")
      (node (ref "J100") (pin "P3") (pinfunction "3_P3") (pintype "passive"))
      (node (ref "R2") (pin "2") (pinfunction "2_2") (pintype "passive"))
    )
    (net (code "40") (name "Net-(J101-2)") (class "Default")
      (node (ref "J101") (pin "P2") (pinfunction "2_P2") (pintype "passive"))
      (node (ref "R35") (pin "1") (pinfunction "1_1") (pintype "passive"))
    )
    (net (code "41") (name "Net-(J101-3)") (class "Default")
      (node (ref "J101") (pin "P3") (pinfunction "3_P3") (pintype "passive"))
      (node (ref "R37") (pin "2") (pinfunction "2_2") (pintype "passive"))
    )
    (net (code "42") (name "Net-(J102-3)") (class "Default")
      (node (ref "J102") (pin "P3") (pinfunction "3_P3") (pintype "passive"))
      (node (ref "R4") (pin "2") (pinfunction "2_2") (pintype "passive"))
    )
    (net (code "43") (name "Net-(J103-3)") (class "Default")
      (node (ref "J103") (pin "P3") (pinfunction "3_P3") (pintype "passive"))
      (node (ref "R12") (pin "2") (pinfunction "2_2") (pintype "passive"))
    )
    (net (code "44") (name "Net-(J104-2)") (class "Default")
      (node (ref "J104") (pin "P2") (pinfunction "2_P2") (pintype "passive"))
      (node (ref "R17") (pin "2") (pinfunction "2_2") (pintype "passive"))
    )
    (net (code "45") (name "Net-(J104-3)") (class "Default")
      (node (ref "J104") (pin "P3") (pinfunction "3_P3") (pintype "passive"))
      (node (ref "R38") (pin "1") (pinfunction "1_1") (pintype "passive"))
    )
    (net (code "46") (name "Net-(J105-2)") (class "Default")
      (node (ref "J105") (pin "P2") (pinfunction "2_P2") (pintype "passive"))
      (node (ref "R19") (pin "2") (pinfunction "2_2") (pintype "passive"))
    )
    (net (code "47") (name "Net-(J105-3)") (class "Default")
      (node (ref "J105") (pin "P3") (pinfunction "3_P3") (pintype "passive"))
      (node (ref "R32") (pin "1") (pinfunction "1_1") (pintype "passive"))
    )
    (net (code "48") (name "Net-(JP1-Pad10)") (class "Default")
      (node (ref "JP1") (pin "10") (pinfunction "10_10") (pintype "passive"))
      (node (ref "JP1") (pin "9") (pinfunction "9_9") (pintype "passive"))
      (node (ref "P1") (pin "2") (pinfunction "2_2") (pintype "bidirectional"))
    )
    (net (code "49") (name "Net-(L1-Pad2)") (class "Default")
      (node (ref "L1") (pin "2") (pinfunction "2_2") (pintype "passive"))
      (node (ref "P1") (pin "1") (pinfunction "1_1") (pintype "bidirectional"))
    )
    (net (code "50") (name "Net-(POT100-A)") (class "Default")
      (node (ref "POT100") (pin "1") (pinfunction "A_1") (pintype "passive"))
      (node (ref "R25") (pin "2") (pinfunction "2_2") (pintype "passive"))
    )
    (net (code "51") (name "Net-(POT101-A)") (class "Default")
      (node (ref "POT101") (pin "1") (pinfunction "A_1") (pintype "passive"))
      (node (ref "R26") (pin "2") (pinfunction "2_2") (pintype "passive"))
    )
    (net (code "52") (name "Net-(R100-S)") (class "Default")
      (node (ref "R100") (pin "P$2") (pinfunction "S_P$2") (pintype "passive"))
      (node (ref "R2") (pin "1") (pinfunction "1_1") (pintype "passive"))
    )
    (net (code "53") (name "Net-(R101-S)") (class "Default")
      (node (ref "R101") (pin "P$2") (pinfunction "S_P$2") (pintype "passive"))
      (node (ref "R37") (pin "1") (pinfunction "1_1") (pintype "passive"))
    )
    (net (code "54") (name "OUT") (class "Default")
      (node (ref "IC4") (pin "8") (pinfunction "OUT_8") (pintype "output"))
      (node (ref "J1") (pin "1") (pinfunction "1_1") (pintype "passive"))
      (node (ref "R20") (pin "1") (pinfunction "1_1") (pintype "passive"))
    )
    (net (code "55") (name "VCC") (class "Default")
      (node (ref "C12") (pin "1") (pinfunction "1_1") (pintype "passive"))
      (node (ref "C19") (pin "1") (pinfunction "1_1") (pintype "passive"))
      (node (ref "C2") (pin "+") (pinfunction "+_+") (pintype "passive"))
      (node (ref "C21") (pin "1") (pinfunction "1_1") (pintype "passive"))
      (node (ref "C4") (pin "1") (pinfunction "1_1") (pintype "passive"))
      (node (ref "IC2") (pin "16") (pinfunction "V+_16") (pintype "power_in"))
      (node (ref "IC3") (pin "4") (pinfunction "V+_4") (pintype "power_in"))
      (node (ref "IC4") (pin "4") (pinfunction "V+_4") (pintype "power_in"))
      (node (ref "IC5") (pin "8") (pinfunction "V+_8") (pintype "power_in"))
      (node (ref "L2") (pin "1") (pinfunction "1_1") (pintype "passive"))
      (node (ref "R33") (pin "1") (pinfunction "1_1") (pintype "passive"))
    )
    (net (code "56") (name "VEE") (class "Default")
      (node (ref "C10") (pin "2") (pinfunction "2_2") (pintype "passive"))
      (node (ref "C15") (pin "2") (pinfunction "2_2") (pintype "passive"))
      (node (ref "C18") (pin "2") (pinfunction "2_2") (pintype "passive"))
      (node (ref "C22") (pin "2") (pinfunction "2_2") (pintype "passive"))
      (node (ref "C3") (pin "-") (pinfunction "-_-") (pintype "passive"))
      (node (ref "D2") (pin "A") (pinfunction "A_A") (pintype "passive"))
      (node (ref "IC2") (pin "9") (pinfunction "V-_9") (pintype "power_in"))
      (node (ref "IC3") (pin "11") (pinfunction "V-_11") (pintype "power_in"))
      (node (ref "IC4") (pin "11") (pinfunction "V-_11") (pintype "power_in"))
      (node (ref "IC5") (pin "4") (pinfunction "V-_4") (pintype "power_in"))
      (node (ref "L1") (pin "1") (pinfunction "1_1") (pintype "passive"))
      (node (ref "R1") (pin "1") (pinfunction "1_1") (pintype "passive"))
    )
    (net (code "57") (name "unconnected-(IC2E-MODE-Pad1)") (class "Default")
      (node (ref "IC2") (pin "1") (pinfunction "MODE_1") (pintype "input"))
    )
  )
)
